# sd_slot.net
KiCad netlist of a schematic drawn in Altium Designer
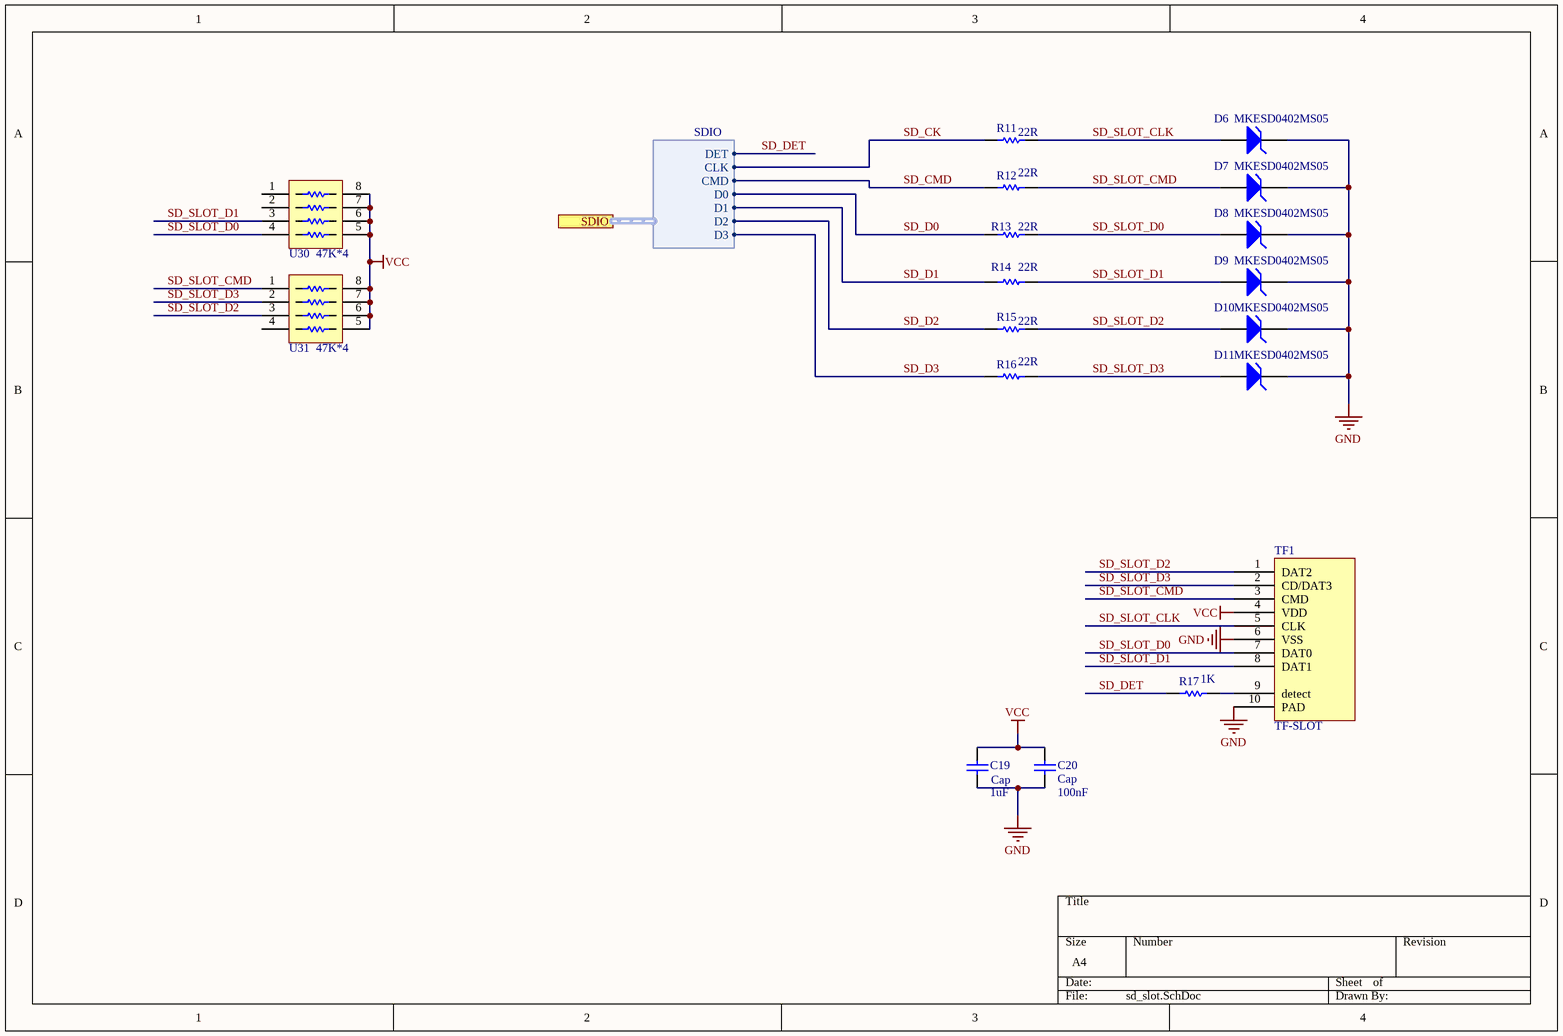
[diagram p0: sd_slot.SchDoc]

(export (version "E")
  (design (tool "Eeschema 10.0.6"))
  (components
    (comp (ref "C19")
      (value "Cap")
      (footprint "6-0805_L")
      (description "Capacitor")
      (fields (field (name "ALTIUM_VALUE") "1uF") (field (name "PUBLISHER") "Altium Limited"))
      (libsource (lib "Miscellaneous Devices") (part "Cap"))
    )
    (comp (ref "C20")
      (value "Cap")
      (footprint "0402")
      (description "Capacitor")
      (fields (field (name "ALTIUM_VALUE") "100nF") (field (name "PUBLISHER") "Altium Limited"))
      (libsource (lib "Miscellaneous Devices") (part "Cap"))
    )
    (comp (ref "D6")
      (value "MKESD0402MS05")
      (footprint "0402")
      (description "Zener Diode")
      (fields (field (name "PUBLISHER") "Altium Limited"))
      (libsource (lib "Miscellaneous Devices") (part "D Zener"))
    )
    (comp (ref "D7")
      (value "MKESD0402MS05")
      (footprint "0402")
      (description "Zener Diode")
      (fields (field (name "PUBLISHER") "Altium Limited"))
      (libsource (lib "Miscellaneous Devices") (part "D Zener"))
    )
    (comp (ref "D8")
      (value "MKESD0402MS05")
      (footprint "0402")
      (description "Zener Diode")
      (fields (field (name "PUBLISHER") "Altium Limited"))
      (libsource (lib "Miscellaneous Devices") (part "D Zener"))
    )
    (comp (ref "D9")
      (value "MKESD0402MS05")
      (footprint "0402")
      (description "Zener Diode")
      (fields (field (name "PUBLISHER") "Altium Limited"))
      (libsource (lib "Miscellaneous Devices") (part "D Zener"))
    )
    (comp (ref "D10")
      (value "MKESD0402MS05")
      (footprint "0402")
      (description "Zener Diode")
      (fields (field (name "PUBLISHER") "Altium Limited"))
      (libsource (lib "Miscellaneous Devices") (part "D Zener"))
    )
    (comp (ref "D11")
      (value "MKESD0402MS05")
      (footprint "0402")
      (description "Zener Diode")
      (fields (field (name "PUBLISHER") "Altium Limited"))
      (libsource (lib "Miscellaneous Devices") (part "D Zener"))
    )
    (comp (ref "R11")
      (value "22R")
      (footprint "0402")
      (description "Resistor")
      (fields (field (name "Comment") "Res1") (field (name "PUBLISHER") "Altium Limited"))
      (libsource (lib "Miscellaneous Devices") (part "Res1"))
    )
    (comp (ref "R12")
      (value "22R")
      (footprint "0402")
      (description "Resistor")
      (fields (field (name "Comment") "Res1") (field (name "PUBLISHER") "Altium Limited"))
      (libsource (lib "Miscellaneous Devices") (part "Res1"))
    )
    (comp (ref "R13")
      (value "22R")
      (footprint "0402")
      (description "Resistor")
      (fields (field (name "Comment") "Res1") (field (name "PUBLISHER") "Altium Limited"))
      (libsource (lib "Miscellaneous Devices") (part "Res1"))
    )
    (comp (ref "R14")
      (value "22R")
      (footprint "0402")
      (description "Resistor")
      (fields (field (name "Comment") "Res1") (field (name "PUBLISHER") "Altium Limited"))
      (libsource (lib "Miscellaneous Devices") (part "Res1"))
    )
    (comp (ref "R15")
      (value "22R")
      (footprint "0402")
      (description "Resistor")
      (fields (field (name "Comment") "Res1") (field (name "PUBLISHER") "Altium Limited"))
      (libsource (lib "Miscellaneous Devices") (part "Res1"))
    )
    (comp (ref "R16")
      (value "22R")
      (footprint "0402")
      (description "Resistor")
      (fields (field (name "Comment") "Res1") (field (name "PUBLISHER") "Altium Limited"))
      (libsource (lib "Miscellaneous Devices") (part "Res1"))
    )
    (comp (ref "R17")
      (value "1K")
      (footprint "0402")
      (description "Resistor")
      (fields (field (name "Comment") "Res1") (field (name "PUBLISHER") "Altium Limited"))
      (libsource (lib "Miscellaneous Devices") (part "Res1"))
    )
    (comp (ref "TF1") (value "TF-SLOT") (footprint "Micro SD") (libsource (lib "cl_sch") (part "TF-SLOT")))
    (comp (ref "U30")
      (value "47K*4")
      (footprint "0603_RES_BATCH")
      (libsource (lib "cl_sch") (part "RES_BATCH"))
    )
    (comp (ref "U31")
      (value "47K*4")
      (footprint "0603_RES_BATCH")
      (libsource (lib "cl_sch") (part "RES_BATCH"))
    )
  )
  (nets
    (net (code "2") (name "/SD_CK") (class "Default")
      (node (ref "R11") (pin "2") (pinfunction "2_2") (pintype "passive"))
    )
    (net (code "3") (name "/SD_CMD") (class "Default")
      (node (ref "R12") (pin "2") (pinfunction "2_2") (pintype "passive"))
    )
    (net (code "4") (name "/SD_D0") (class "Default")
      (node (ref "R13") (pin "2") (pinfunction "2_2") (pintype "passive"))
    )
    (net (code "5") (name "/SD_D1") (class "Default")
      (node (ref "R14") (pin "2") (pinfunction "2_2") (pintype "passive"))
    )
    (net (code "6") (name "/SD_D2") (class "Default")
      (node (ref "R15") (pin "2") (pinfunction "2_2") (pintype "passive"))
    )
    (net (code "7") (name "/SD_D3") (class "Default")
      (node (ref "R16") (pin "2") (pinfunction "2_2") (pintype "passive"))
    )
    (net (code "8") (name "/SD_DET") (class "Default")
      (node (ref "R17") (pin "2") (pinfunction "2_2") (pintype "passive"))
    )
    (net (code "9") (name "/SD_SLOT_CLK") (class "Default")
      (node (ref "D6") (pin "1") (pinfunction "A_1") (pintype "passive"))
      (node (ref "R11") (pin "1") (pinfunction "1_1") (pintype "passive"))
      (node (ref "TF1") (pin "5") (pinfunction "CLK_5") (pintype "passive"))
    )
    (net (code "10") (name "/SD_SLOT_CMD") (class "Default")
      (node (ref "D7") (pin "1") (pinfunction "A_1") (pintype "passive"))
      (node (ref "R12") (pin "1") (pinfunction "1_1") (pintype "passive"))
      (node (ref "TF1") (pin "3") (pinfunction "CMD_3") (pintype "passive"))
      (node (ref "U31") (pin "1") (pinfunction "1_1") (pintype "passive"))
    )
    (net (code "11") (name "/SD_SLOT_D0") (class "Default")
      (node (ref "D8") (pin "1") (pinfunction "A_1") (pintype "passive"))
      (node (ref "R13") (pin "1") (pinfunction "1_1") (pintype "passive"))
      (node (ref "TF1") (pin "7") (pinfunction "DAT0_7") (pintype "passive"))
      (node (ref "U30") (pin "4") (pinfunction "4_4") (pintype "passive"))
    )
    (net (code "12") (name "/SD_SLOT_D1") (class "Default")
      (node (ref "D9") (pin "1") (pinfunction "A_1") (pintype "passive"))
      (node (ref "R14") (pin "1") (pinfunction "1_1") (pintype "passive"))
      (node (ref "TF1") (pin "8") (pinfunction "DAT1_8") (pintype "passive"))
      (node (ref "U30") (pin "3") (pinfunction "3_3") (pintype "passive"))
    )
    (net (code "13") (name "/SD_SLOT_D2") (class "Default")
      (node (ref "D10") (pin "1") (pinfunction "A_1") (pintype "passive"))
      (node (ref "R15") (pin "1") (pinfunction "1_1") (pintype "passive"))
      (node (ref "TF1") (pin "1") (pinfunction "DAT2_1") (pintype "passive"))
      (node (ref "U31") (pin "3") (pinfunction "3_3") (pintype "passive"))
    )
    (net (code "14") (name "/SD_SLOT_D3") (class "Default")
      (node (ref "D11") (pin "1") (pinfunction "A_1") (pintype "passive"))
      (node (ref "R16") (pin "1") (pinfunction "1_1") (pintype "passive"))
      (node (ref "TF1") (pin "2") (pinfunction "CD/DAT3_2") (pintype "passive"))
      (node (ref "U31") (pin "2") (pinfunction "2_2") (pintype "passive"))
    )
    (net (code "16") (name "GND") (class "Default")
      (node (ref "C19") (pin "1") (pinfunction "1_1") (pintype "passive"))
      (node (ref "C20") (pin "1") (pinfunction "1_1") (pintype "passive"))
      (node (ref "D10") (pin "2") (pinfunction "K_2") (pintype "passive"))
      (node (ref "D11") (pin "2") (pinfunction "K_2") (pintype "passive"))
      (node (ref "D6") (pin "2") (pinfunction "K_2") (pintype "passive"))
      (node (ref "D7") (pin "2") (pinfunction "K_2") (pintype "passive"))
      (node (ref "D8") (pin "2") (pinfunction "K_2") (pintype "passive"))
      (node (ref "D9") (pin "2") (pinfunction "K_2") (pintype "passive"))
      (node (ref "TF1") (pin "10") (pinfunction "PAD_10") (pintype "passive"))
      (node (ref "TF1") (pin "6") (pinfunction "VSS_6") (pintype "passive"))
    )
    (net (code "17") (name "Net-(TF1-detect)") (class "Default")
      (node (ref "R17") (pin "1") (pinfunction "1_1") (pintype "passive"))
      (node (ref "TF1") (pin "9") (pinfunction "detect_9") (pintype "passive"))
    )
    (net (code "18") (name "VCC") (class "Default")
      (node (ref "C19") (pin "2") (pinfunction "2_2") (pintype "passive"))
      (node (ref "C20") (pin "2") (pinfunction "2_2") (pintype "passive"))
      (node (ref "TF1") (pin "4") (pinfunction "VDD_4") (pintype "passive"))
      (node (ref "U30") (pin "5") (pinfunction "5_5") (pintype "passive"))
      (node (ref "U30") (pin "6") (pinfunction "6_6") (pintype "passive"))
      (node (ref "U30") (pin "7") (pinfunction "7_7") (pintype "passive"))
      (node (ref "U30") (pin "8") (pinfunction "8_8") (pintype "passive"))
      (node (ref "U31") (pin "5") (pinfunction "5_5") (pintype "passive"))
      (node (ref "U31") (pin "6") (pinfunction "6_6") (pintype "passive"))
      (node (ref "U31") (pin "7") (pinfunction "7_7") (pintype "passive"))
      (node (ref "U31") (pin "8") (pinfunction "8_8") (pintype "passive"))
    )
    (net (code "19") (name "unconnected-(U30-Pad1)") (class "Default")
      (node (ref "U30") (pin "1") (pinfunction "1_1") (pintype "passive"))
    )
    (net (code "20") (name "unconnected-(U30-Pad2)") (class "Default")
      (node (ref "U30") (pin "2") (pinfunction "2_2") (pintype "passive"))
    )
    (net (code "21") (name "unconnected-(U31-Pad4)") (class "Default")
      (node (ref "U31") (pin "4") (pinfunction "4_4") (pintype "passive"))
    )
  )
)
